# CH579M-R1.net
KiCad netlist of a schematic drawn in Altium Designer
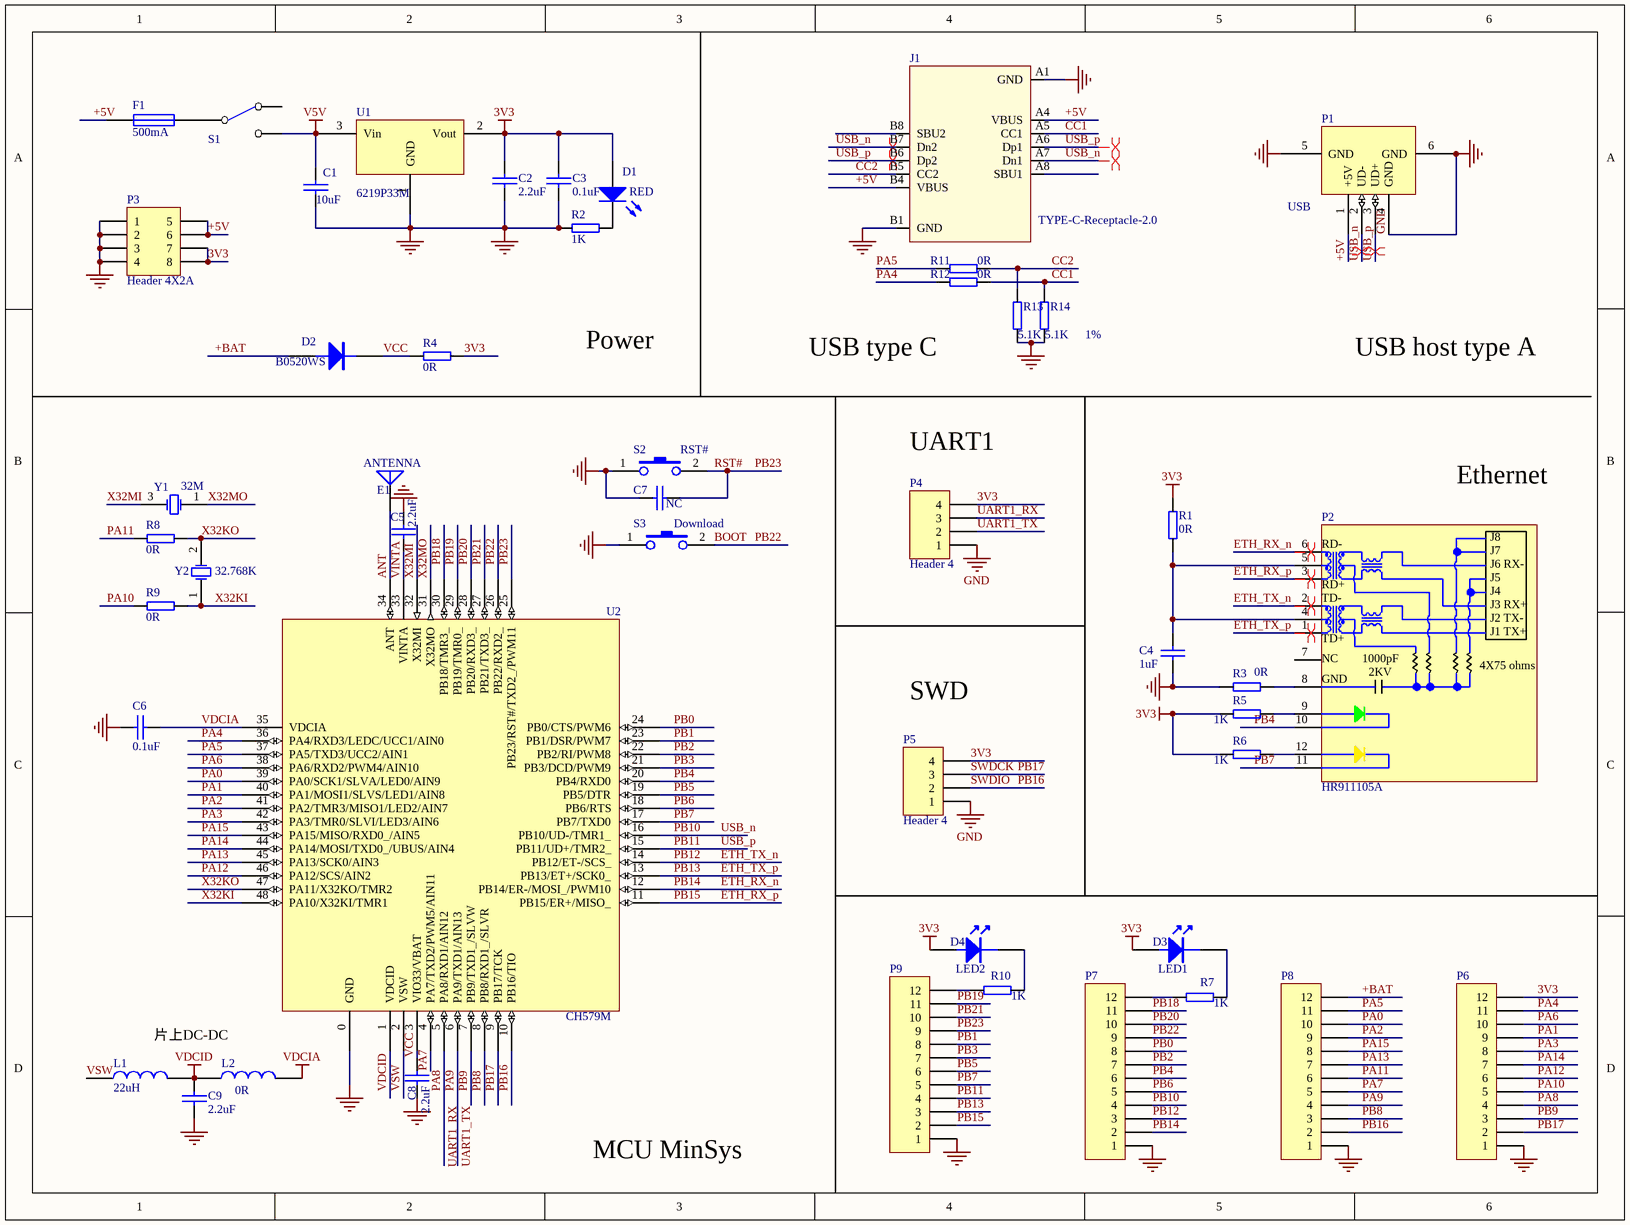
[diagram p0: CH579M-R1.SchDoc]

(export (version "E")
  (design (tool "Eeschema 10.0.6"))
  (components
    (comp (ref "C1")
      (value "10uF")
      (footprint "3216")
      (description "Capacitor")
      (libsource (lib "") (part "CAP_1"))
    )
    (comp (ref "C2")
      (value "2.2uF")
      (footprint "0603")
      (description "Capacitor")
      (libsource (lib "") (part "CAP_1"))
    )
    (comp (ref "C3")
      (value "0.1uF")
      (footprint "0603")
      (description "Capacitor")
      (libsource (lib "") (part "CAP_1"))
    )
    (comp (ref "C4")
      (value "1uF")
      (footprint "0603")
      (description "Capacitor")
      (libsource (lib "") (part "CAP_1"))
    )
    (comp (ref "C5")
      (value "2.2uF")
      (footprint "0603")
      (description "Capacitor")
      (libsource (lib "*") (part "CAP"))
    )
    (comp (ref "C6")
      (value "0.1uF")
      (footprint "0603")
      (description "Capacitor")
      (libsource (lib "*") (part "CAP"))
    )
    (comp (ref "C7")
      (value "NC")
      (footprint "0603")
      (description "Capacitor")
      (libsource (lib "*") (part "CAP"))
    )
    (comp (ref "C8")
      (value "2.2uF")
      (footprint "0603")
      (description "Capacitor")
      (libsource (lib "*") (part "CAP"))
    )
    (comp (ref "C9")
      (value "2.2uF")
      (footprint "0603")
      (description "Capacitor")
      (libsource (lib "*") (part "CAP"))
    )
    (comp (ref "D1")
      (value "RED")
      (footprint "0603+")
      (description "Typical INFRARED GaAs LED")
      (fields (field (name "PUBLISHER") "Altium Limited"))
      (libsource (lib "*") (part "LED0"))
    )
    (comp (ref "D2")
      (value "B0520WS")
      (footprint "SOD323")
      (description "Diode")
      (libsource (lib "*") (part "DIODE"))
    )
    (comp (ref "D3") (value "LED1") (footprint "0603+") (libsource (lib "*") (part "LED")))
    (comp (ref "D4") (value "LED2") (footprint "0603+") (libsource (lib "*") (part "LED")))
    (comp (ref "E1")
      (value "ANTENNA")
      (footprint "ANT-F-1-2.4G-1.6")
      (description "Generic Antenna")
      (libsource (lib "*") (part "ANTENNA"))
    )
    (comp (ref "F1")
      (value "500mA")
      (footprint "0805")
      (description "Fuse")
      (libsource (lib "wch_sch_others") (part "FUSE1"))
    )
    (comp (ref "J1")
      (value "TYPE-C-Receptacle-2.0")
      (footprint "TYPE-C-Receptacle-2.0")
      (description "Type-C USB2.0 母座")
      (libsource (lib "Miscellaneous SCH Lib") (part "TYPE-C-Receptacle-2.0"))
    )
    (comp (ref "L1") (value "22uH") (footprint "SMD-2.5*2*1.05") (libsource (lib "*") (part "INDUCTOR")))
    (comp (ref "L2") (value "0R") (footprint "0603") (libsource (lib "*") (part "INDUCTOR")))
    (comp (ref "P1")
      (value "USB")
      (footprint "USBA-L")
      (description "USB Port")
      (libsource (lib "*") (part "USB"))
    )
    (comp (ref "P2") (value "HR911105A") (footprint "HR911105A") (libsource (lib "*") (part "HR911105A")))
    (comp (ref "P3")
      (value "Header 4X2A")
      (footprint "IDC8")
      (description "Header, 4-Pin, Dual row")
      (fields (field (name "PUBLISHER") "Altium Limited"))
      (libsource (lib "Miscellaneous Connectors") (part "Header 4X2A"))
    )
    (comp (ref "P4")
      (value "Header 4")
      (footprint "HDR1X4")
      (description "Header, 4-Pin")
      (fields (field (name "PUBLISHER") "Altium Limited"))
      (libsource (lib "Miscellaneous Connectors") (part "Header 4"))
    )
    (comp (ref "P5")
      (value "Header 4")
      (footprint "HDR1X4")
      (description "Header, 4-Pin")
      (fields (field (name "PUBLISHER") "Altium Limited"))
      (libsource (lib "Miscellaneous Connectors") (part "Header 4"))
    )
    (comp (ref "P6")
      (value "Header 12")
      (footprint "SIP12 - 40mil")
      (description "Header, 12-Pin")
      (fields (field (name "PUBLISHER") "Altium Limited"))
      (libsource (lib "Miscellaneous Connectors") (part "Header 12"))
    )
    (comp (ref "P7")
      (value "Header 12")
      (footprint "SIP12 - 40mil")
      (description "Header, 12-Pin")
      (fields (field (name "PUBLISHER") "Altium Limited"))
      (libsource (lib "Miscellaneous Connectors") (part "Header 12"))
    )
    (comp (ref "P8")
      (value "Header 12")
      (footprint "SIP12 - 40mil")
      (description "Header, 12-Pin")
      (fields (field (name "PUBLISHER") "Altium Limited"))
      (libsource (lib "Miscellaneous Connectors") (part "Header 12"))
    )
    (comp (ref "P9")
      (value "Header 12")
      (footprint "SIP12 - 40mil")
      (description "Header, 12-Pin")
      (fields (field (name "PUBLISHER") "Altium Limited"))
      (libsource (lib "Miscellaneous Connectors") (part "Header 12"))
    )
    (comp (ref "R1") (value "0R") (footprint "0603") (libsource (lib "wch_sch_others") (part "RES")))
    (comp (ref "R2") (value "1K") (footprint "0603") (libsource (lib "wch_sch_others") (part "RES")))
    (comp (ref "R3") (value "0R") (footprint "0603") (libsource (lib "wch_sch_others") (part "RES")))
    (comp (ref "R4") (value "0R") (footprint "0603") (libsource (lib "wch_sch_others") (part "RES")))
    (comp (ref "R5") (value "1K") (footprint "0603") (libsource (lib "wch_sch_others") (part "RES")))
    (comp (ref "R6") (value "1K") (footprint "0603") (libsource (lib "wch_sch_others") (part "RES")))
    (comp (ref "R7") (value "1K") (footprint "0603") (libsource (lib "wch_sch_others") (part "RES")))
    (comp (ref "R8") (value "0R") (footprint "0603") (libsource (lib "wch_sch_others") (part "RES")))
    (comp (ref "R9") (value "0R") (footprint "0603") (libsource (lib "wch_sch_others") (part "RES")))
    (comp (ref "R10") (value "1K") (footprint "0603") (libsource (lib "wch_sch_others") (part "RES")))
    (comp (ref "R11") (value "0R") (footprint "0603") (libsource (lib "wch_sch_others") (part "RES")))
    (comp (ref "R12") (value "0R") (footprint "0603") (libsource (lib "wch_sch_others") (part "RES")))
    (comp (ref "R13") (value "5.1K") (footprint "0603") (libsource (lib "wch_sch_others") (part "RES")))
    (comp (ref "R14") (value "5.1K") (footprint "0603") (libsource (lib "wch_sch_others") (part "RES")))
    (comp (ref "S1") (value "SW SPDT") (footprint "KEY_B") (libsource (lib "*") (part "SW SPDT")))
    (comp (ref "S2")
      (value "RST#")
      (footprint "SMD_6.1x3.65x2.5mm-KEY")
      (libsource (lib "wch_sch_others") (part "KEY1"))
    )
    (comp (ref "S3")
      (value "Download")
      (footprint "SMD_6.1x3.65x2.5mm-KEY")
      (libsource (lib "wch_sch_others") (part "KEY1"))
    )
    (comp (ref "U1")
      (value "6219P33M")
      (footprint "SOT-23")
      (libsource (lib "wch_sch_others") (part "6219P33M"))
    )
    (comp (ref "U2")
      (value "CH579M")
      (footprint "QFN48_5X5")
      (description "ARM M0 MCU with BLE+Zigbee+Ethernet+USB")
      (libsource (lib "*") (part "CH579M"))
    )
    (comp (ref "Y1")
      (value "32M")
      (footprint "3225")
      (description "Crystal Oscillator")
      (fields (field (name "PUBLISHER") "Altium Limited"))
      (libsource (lib "*") (part "XTAL"))
    )
    (comp (ref "Y2")
      (value "32.768K")
      (footprint "fc-135")
      (description "Crystal Oscillator")
      (fields (field (name "PUBLISHER") "Altium Limited"))
      (libsource (lib "") (part "XTAL_1"))
    )
  )
  (nets
    (net (code "1") (name "/+5V") (class "Default")
      (node (ref "F1") (pin "1") (pinfunction "1_1") (pintype "passive"))
      (node (ref "J1") (pin "A4") (pinfunction "VBUS_A4") (pintype "passive"))
      (node (ref "J1") (pin "B4") (pinfunction "VBUS_B4") (pintype "passive"))
      (node (ref "P1") (pin "1") (pinfunction "+5V_1") (pintype "power_in"))
      (node (ref "P3") (pin "5") (pinfunction "5_5") (pintype "passive"))
      (node (ref "P3") (pin "6") (pinfunction "6_6") (pintype "passive"))
    )
    (net (code "2") (name "/+BAT") (class "Default")
      (node (ref "D2") (pin "1") (pinfunction "A_1") (pintype "passive"))
      (node (ref "P8") (pin "12") (pinfunction "12_12") (pintype "passive"))
    )
    (net (code "3") (name "/ANT") (class "Default")
      (node (ref "E1") (pin "1") (pinfunction "A_1") (pintype "passive"))
      (node (ref "U2") (pin "34") (pinfunction "ANT_34") (pintype "bidirectional"))
    )
    (net (code "4") (name "/BOOT") (class "Default")
      (node (ref "P7") (pin "9") (pinfunction "9_9") (pintype "passive"))
      (node (ref "S3") (pin "2") (pinfunction "2_2") (pintype "passive"))
      (node (ref "U2") (pin "26") (pinfunction "PB22/RXD2__26") (pintype "bidirectional"))
    )
    (net (code "5") (name "/CC1") (class "Default")
      (node (ref "J1") (pin "A5") (pinfunction "CC1_A5") (pintype "passive"))
      (node (ref "R12") (pin "2") (pintype "passive"))
      (node (ref "R14") (pin "1") (pintype "passive"))
    )
    (net (code "6") (name "/CC2") (class "Default")
      (node (ref "J1") (pin "B5") (pinfunction "CC2_B5") (pintype "passive"))
      (node (ref "R11") (pin "2") (pintype "passive"))
      (node (ref "R13") (pin "1") (pintype "passive"))
    )
    (net (code "7") (name "/ETH_RX_n") (class "Default")
      (node (ref "P2") (pin "6") (pintype "passive"))
      (node (ref "P7") (pin "2") (pinfunction "2_2") (pintype "passive"))
      (node (ref "U2") (pin "12") (pinfunction "PB14/ER-/MOSI_/PWM10_12") (pintype "bidirectional"))
    )
    (net (code "8") (name "/ETH_RX_p") (class "Default")
      (node (ref "P2") (pin "3") (pintype "passive"))
      (node (ref "P9") (pin "2") (pinfunction "2_2") (pintype "passive"))
      (node (ref "U2") (pin "11") (pinfunction "PB15/ER+/MISO__11") (pintype "bidirectional"))
    )
    (net (code "9") (name "/ETH_TX_n") (class "Default")
      (node (ref "P2") (pin "2") (pintype "passive"))
      (node (ref "P7") (pin "3") (pinfunction "3_3") (pintype "passive"))
      (node (ref "U2") (pin "14") (pinfunction "PB12/ET-/SCS__14") (pintype "bidirectional"))
    )
    (net (code "10") (name "/ETH_TX_p") (class "Default")
      (node (ref "P2") (pin "1") (pintype "passive"))
      (node (ref "P9") (pin "3") (pinfunction "3_3") (pintype "passive"))
      (node (ref "U2") (pin "13") (pinfunction "PB13/ET+/SCK0__13") (pintype "bidirectional"))
    )
    (net (code "11") (name "/PA0") (class "Default")
      (node (ref "P8") (pin "10") (pinfunction "10_10") (pintype "passive"))
      (node (ref "U2") (pin "39") (pinfunction "PA0/SCK1/SLVA/LED0/AIN9_39") (pintype "bidirectional"))
    )
    (net (code "12") (name "/PA1") (class "Default")
      (node (ref "P6") (pin "9") (pinfunction "9_9") (pintype "passive"))
      (node (ref "U2") (pin "40") (pinfunction "PA1/MOSI1/SLVS/LED1/AIN8_40") (pintype "bidirectional"))
    )
    (net (code "13") (name "/PA2") (class "Default")
      (node (ref "P8") (pin "9") (pinfunction "9_9") (pintype "passive"))
      (node (ref "U2") (pin "41") (pinfunction "PA2/TMR3/MISO1/LED2/AIN7_41") (pintype "bidirectional"))
    )
    (net (code "14") (name "/PA3") (class "Default")
      (node (ref "P6") (pin "8") (pinfunction "8_8") (pintype "passive"))
      (node (ref "U2") (pin "42") (pinfunction "PA3/TMR0/SLVI/LED3/AIN6_42") (pintype "bidirectional"))
    )
    (net (code "15") (name "/PA4") (class "Default")
      (node (ref "P6") (pin "11") (pinfunction "11_11") (pintype "passive"))
      (node (ref "R12") (pin "1") (pintype "passive"))
      (node (ref "U2") (pin "36") (pinfunction "PA4/RXD3/LEDC/UCC1/AIN0_36") (pintype "bidirectional"))
    )
    (net (code "16") (name "/PA5") (class "Default")
      (node (ref "P8") (pin "11") (pinfunction "11_11") (pintype "passive"))
      (node (ref "R11") (pin "1") (pintype "passive"))
      (node (ref "U2") (pin "37") (pinfunction "PA5/TXD3/UCC2/AIN1_37") (pintype "bidirectional"))
    )
    (net (code "17") (name "/PA6") (class "Default")
      (node (ref "P6") (pin "10") (pinfunction "10_10") (pintype "passive"))
      (node (ref "U2") (pin "38") (pinfunction "PA6/RXD2/PWM4/AIN10_38") (pintype "bidirectional"))
    )
    (net (code "18") (name "/PA7") (class "Default")
      (node (ref "P8") (pin "5") (pinfunction "5_5") (pintype "passive"))
      (node (ref "U2") (pin "4") (pinfunction "PA7/TXD2/PWM5/AIN11_4") (pintype "bidirectional"))
    )
    (net (code "19") (name "/PA8") (class "Default")
      (node (ref "P4") (pin "3") (pinfunction "3_3") (pintype "passive"))
      (node (ref "P6") (pin "4") (pinfunction "4_4") (pintype "passive"))
      (node (ref "U2") (pin "5") (pinfunction "PA8/RXD1/AIN12_5") (pintype "bidirectional"))
    )
    (net (code "20") (name "/PA9") (class "Default")
      (node (ref "P4") (pin "2") (pinfunction "2_2") (pintype "passive"))
      (node (ref "P8") (pin "4") (pinfunction "4_4") (pintype "passive"))
      (node (ref "U2") (pin "6") (pinfunction "PA9/TXD1/AIN13_6") (pintype "bidirectional"))
    )
    (net (code "21") (name "/PA10") (class "Default")
      (node (ref "P6") (pin "5") (pinfunction "5_5") (pintype "passive"))
      (node (ref "R9") (pin "1") (pintype "passive"))
    )
    (net (code "22") (name "/PA11") (class "Default")
      (node (ref "P8") (pin "6") (pinfunction "6_6") (pintype "passive"))
      (node (ref "R8") (pin "1") (pintype "passive"))
    )
    (net (code "23") (name "/PA12") (class "Default")
      (node (ref "P6") (pin "6") (pinfunction "6_6") (pintype "passive"))
      (node (ref "U2") (pin "46") (pinfunction "PA12/SCS/AIN2_46") (pintype "bidirectional"))
    )
    (net (code "24") (name "/PA13") (class "Default")
      (node (ref "P8") (pin "7") (pinfunction "7_7") (pintype "passive"))
      (node (ref "U2") (pin "45") (pinfunction "PA13/SCK0/AIN3_45") (pintype "bidirectional"))
    )
    (net (code "25") (name "/PA14") (class "Default")
      (node (ref "P6") (pin "7") (pinfunction "7_7") (pintype "passive"))
      (node (ref "U2") (pin "44") (pinfunction "PA14/MOSI/TXD0_/UBUS/AIN4_44") (pintype "bidirectional"))
    )
    (net (code "26") (name "/PA15") (class "Default")
      (node (ref "P8") (pin "8") (pinfunction "8_8") (pintype "passive"))
      (node (ref "U2") (pin "43") (pinfunction "PA15/MISO/RXD0_/AIN5_43") (pintype "bidirectional"))
    )
    (net (code "27") (name "/PB0") (class "Default")
      (node (ref "P7") (pin "8") (pinfunction "8_8") (pintype "passive"))
      (node (ref "U2") (pin "24") (pinfunction "PB0/CTS/PWM6_24") (pintype "bidirectional"))
    )
    (net (code "28") (name "/PB1") (class "Default")
      (node (ref "P9") (pin "8") (pinfunction "8_8") (pintype "passive"))
      (node (ref "U2") (pin "23") (pinfunction "PB1/DSR/PWM7_23") (pintype "bidirectional"))
    )
    (net (code "29") (name "/PB2") (class "Default")
      (node (ref "P7") (pin "7") (pinfunction "7_7") (pintype "passive"))
      (node (ref "U2") (pin "22") (pinfunction "PB2/RI/PWM8_22") (pintype "bidirectional"))
    )
    (net (code "30") (name "/PB3") (class "Default")
      (node (ref "P9") (pin "7") (pinfunction "7_7") (pintype "passive"))
      (node (ref "U2") (pin "21") (pinfunction "PB3/DCD/PWM9_21") (pintype "bidirectional"))
    )
    (net (code "31") (name "/PB4") (class "Default")
      (node (ref "P2") (pin "10") (pintype "passive"))
      (node (ref "P7") (pin "6") (pinfunction "6_6") (pintype "passive"))
      (node (ref "U2") (pin "20") (pinfunction "PB4/RXD0_20") (pintype "bidirectional"))
    )
    (net (code "32") (name "/PB5") (class "Default")
      (node (ref "P9") (pin "6") (pinfunction "6_6") (pintype "passive"))
      (node (ref "U2") (pin "19") (pinfunction "PB5/DTR_19") (pintype "bidirectional"))
    )
    (net (code "33") (name "/PB6") (class "Default")
      (node (ref "P7") (pin "5") (pinfunction "5_5") (pintype "passive"))
      (node (ref "U2") (pin "18") (pinfunction "PB6/RTS_18") (pintype "bidirectional"))
    )
    (net (code "34") (name "/PB7") (class "Default")
      (node (ref "P2") (pin "11") (pintype "passive"))
      (node (ref "P9") (pin "5") (pinfunction "5_5") (pintype "passive"))
      (node (ref "U2") (pin "17") (pinfunction "PB7/TXD0_17") (pintype "bidirectional"))
    )
    (net (code "35") (name "/PB8") (class "Default")
      (node (ref "P8") (pin "3") (pinfunction "3_3") (pintype "passive"))
      (node (ref "U2") (pin "8") (pinfunction "PB8/RXD1_/SLVR_8") (pintype "bidirectional"))
    )
    (net (code "36") (name "/PB9") (class "Default")
      (node (ref "P6") (pin "3") (pinfunction "3_3") (pintype "passive"))
      (node (ref "U2") (pin "7") (pinfunction "PB9/TXD1_/SLVW_7") (pintype "bidirectional"))
    )
    (net (code "37") (name "/PB10") (class "Default")
      (node (ref "J1") (pin "A7") (pinfunction "Dn1_A7") (pintype "passive"))
      (node (ref "J1") (pin "B7") (pinfunction "Dn2_B7") (pintype "passive"))
      (node (ref "P1") (pin "2") (pinfunction "UD-_2") (pintype "bidirectional"))
      (node (ref "P7") (pin "4") (pinfunction "4_4") (pintype "passive"))
      (node (ref "U2") (pin "16") (pinfunction "PB10/UD-/TMR1__16") (pintype "bidirectional"))
    )
    (net (code "38") (name "/PB11") (class "Default")
      (node (ref "J1") (pin "A6") (pinfunction "Dp1_A6") (pintype "passive"))
      (node (ref "J1") (pin "B6") (pinfunction "Dp2_B6") (pintype "passive"))
      (node (ref "P1") (pin "3") (pinfunction "UD+_3") (pintype "bidirectional"))
      (node (ref "P9") (pin "4") (pinfunction "4_4") (pintype "passive"))
      (node (ref "U2") (pin "15") (pinfunction "PB11/UD+/TMR2__15") (pintype "bidirectional"))
    )
    (net (code "39") (name "/PB16") (class "Default")
      (node (ref "P5") (pin "2") (pinfunction "2_2") (pintype "passive"))
      (node (ref "P8") (pin "2") (pinfunction "2_2") (pintype "passive"))
      (node (ref "U2") (pin "10") (pinfunction "PB16/TIO_10") (pintype "bidirectional"))
    )
    (net (code "40") (name "/PB17") (class "Default")
      (node (ref "P5") (pin "3") (pinfunction "3_3") (pintype "passive"))
      (node (ref "P6") (pin "2") (pinfunction "2_2") (pintype "passive"))
      (node (ref "U2") (pin "9") (pinfunction "PB17/TCK_9") (pintype "bidirectional"))
    )
    (net (code "41") (name "/PB18") (class "Default")
      (node (ref "P7") (pin "11") (pinfunction "11_11") (pintype "passive"))
      (node (ref "U2") (pin "30") (pinfunction "PB18/TMR3__30") (pintype "bidirectional"))
    )
    (net (code "42") (name "/PB19") (class "Default")
      (node (ref "P9") (pin "11") (pinfunction "11_11") (pintype "passive"))
      (node (ref "U2") (pin "29") (pinfunction "PB19/TMR0__29") (pintype "bidirectional"))
    )
    (net (code "43") (name "/PB20") (class "Default")
      (node (ref "P7") (pin "10") (pinfunction "10_10") (pintype "passive"))
      (node (ref "U2") (pin "28") (pinfunction "PB20/RXD3__28") (pintype "bidirectional"))
    )
    (net (code "44") (name "/PB21") (class "Default")
      (node (ref "P9") (pin "10") (pinfunction "10_10") (pintype "passive"))
      (node (ref "U2") (pin "27") (pinfunction "PB21/TXD3__27") (pintype "bidirectional"))
    )
    (net (code "45") (name "/PB23") (class "Default")
      (node (ref "C7") (pin "2") (pinfunction "2_2") (pintype "passive"))
      (node (ref "P9") (pin "9") (pinfunction "9_9") (pintype "passive"))
      (node (ref "S2") (pin "2") (pinfunction "2_2") (pintype "passive"))
      (node (ref "U2") (pin "25") (pinfunction "PB23/RST#/TXD2_/PWM11_25") (pintype "bidirectional"))
    )
    (net (code "46") (name "/VCC") (class "Default")
      (node (ref "C8") (pin "2") (pinfunction "2_2") (pintype "passive"))
      (node (ref "D2") (pin "2") (pinfunction "K_2") (pintype "passive"))
      (node (ref "R4") (pin "2") (pintype "passive"))
      (node (ref "U2") (pin "3") (pinfunction "VIO33/VBAT_3") (pintype "power_in"))
    )
    (net (code "47") (name "/VINTA") (class "Default")
      (node (ref "C5") (pin "1") (pinfunction "1_1") (pintype "passive"))
      (node (ref "U2") (pin "33") (pinfunction "VINTA_33") (pintype "power_in"))
    )
    (net (code "48") (name "/VSW") (class "Default")
      (node (ref "L1") (pin "1") (pinfunction "1_1") (pintype "passive"))
      (node (ref "U2") (pin "2") (pinfunction "VSW_2") (pintype "power_in"))
    )
    (net (code "49") (name "/X32KI") (class "Default")
      (node (ref "R9") (pin "2") (pintype "passive"))
      (node (ref "U2") (pin "48") (pinfunction "PA10/X32KI/TMR1_48") (pintype "bidirectional"))
      (node (ref "Y2") (pin "1") (pinfunction "OSC1_1") (pintype "passive"))
    )
    (net (code "50") (name "/X32KO") (class "Default")
      (node (ref "R8") (pin "2") (pintype "passive"))
      (node (ref "U2") (pin "47") (pinfunction "PA11/X32KO/TMR2_47") (pintype "bidirectional"))
      (node (ref "Y2") (pin "2") (pinfunction "OSC2_2") (pintype "passive"))
    )
    (net (code "51") (name "/X32MI") (class "Default")
      (node (ref "U2") (pin "32") (pinfunction "X32MI_32") (pintype "input"))
      (node (ref "Y1") (pin "3") (pinfunction "OSC2_3") (pintype "passive"))
    )
    (net (code "52") (name "/X32MO") (class "Default")
      (node (ref "U2") (pin "31") (pinfunction "X32MO_31") (pintype "output"))
      (node (ref "Y1") (pin "1") (pinfunction "OSC1_1") (pintype "passive"))
    )
    (net (code "53") (name "3V3") (class "Default")
      (node (ref "C2") (pin "1") (pinfunction "1_1") (pintype "passive"))
      (node (ref "C3") (pin "1") (pinfunction "1_1") (pintype "passive"))
      (node (ref "D1") (pin "1") (pinfunction "A_1") (pintype "passive"))
      (node (ref "D3") (pin "1") (pinfunction "1_1") (pintype "passive"))
      (node (ref "D4") (pin "1") (pinfunction "1_1") (pintype "passive"))
      (node (ref "P3") (pin "7") (pinfunction "7_7") (pintype "passive"))
      (node (ref "P3") (pin "8") (pinfunction "8_8") (pintype "passive"))
      (node (ref "P4") (pin "4") (pinfunction "4_4") (pintype "passive"))
      (node (ref "P5") (pin "4") (pinfunction "4_4") (pintype "passive"))
      (node (ref "P6") (pin "12") (pinfunction "12_12") (pintype "passive"))
      (node (ref "R1") (pin "2") (pintype "passive"))
      (node (ref "R4") (pin "1") (pintype "passive"))
      (node (ref "R5") (pin "1") (pintype "passive"))
      (node (ref "R6") (pin "1") (pintype "passive"))
      (node (ref "U1") (pin "2") (pinfunction "Vout_2") (pintype "passive"))
    )
    (net (code "54") (name "GND") (class "Default")
      (node (ref "C1") (pin "2") (pinfunction "2_2") (pintype "passive"))
      (node (ref "C2") (pin "2") (pinfunction "2_2") (pintype "passive"))
      (node (ref "C3") (pin "2") (pinfunction "2_2") (pintype "passive"))
      (node (ref "C4") (pin "1") (pinfunction "1_1") (pintype "passive"))
      (node (ref "C5") (pin "2") (pinfunction "2_2") (pintype "passive"))
      (node (ref "C6") (pin "2") (pinfunction "2_2") (pintype "passive"))
      (node (ref "C7") (pin "1") (pinfunction "1_1") (pintype "passive"))
      (node (ref "C8") (pin "1") (pinfunction "1_1") (pintype "passive"))
      (node (ref "C9") (pin "1") (pinfunction "1_1") (pintype "passive"))
      (node (ref "J1") (pin "A1") (pinfunction "GND_A1") (pintype "passive"))
      (node (ref "J1") (pin "B1") (pinfunction "GND_B1") (pintype "passive"))
      (node (ref "P1") (pin "4") (pinfunction "GND_4") (pintype "power_in"))
      (node (ref "P1") (pin "5") (pinfunction "GND_5") (pintype "power_in"))
      (node (ref "P1") (pin "6") (pinfunction "GND_6") (pintype "power_in"))
      (node (ref "P3") (pin "1") (pinfunction "1_1") (pintype "passive"))
      (node (ref "P3") (pin "2") (pinfunction "2_2") (pintype "passive"))
      (node (ref "P3") (pin "3") (pinfunction "3_3") (pintype "passive"))
      (node (ref "P3") (pin "4") (pinfunction "4_4") (pintype "passive"))
      (node (ref "P4") (pin "1") (pinfunction "1_1") (pintype "passive"))
      (node (ref "P5") (pin "1") (pinfunction "1_1") (pintype "passive"))
      (node (ref "P6") (pin "1") (pinfunction "1_1") (pintype "passive"))
      (node (ref "P7") (pin "1") (pinfunction "1_1") (pintype "passive"))
      (node (ref "P8") (pin "1") (pinfunction "1_1") (pintype "passive"))
      (node (ref "P9") (pin "1") (pinfunction "1_1") (pintype "passive"))
      (node (ref "R13") (pin "2") (pintype "passive"))
      (node (ref "R14") (pin "2") (pintype "passive"))
      (node (ref "R2") (pin "2") (pintype "passive"))
      (node (ref "R3") (pin "1") (pintype "passive"))
      (node (ref "S2") (pin "1") (pinfunction "1_1") (pintype "passive"))
      (node (ref "S3") (pin "1") (pinfunction "1_1") (pintype "passive"))
      (node (ref "U1") (pin "1") (pinfunction "GND_1") (pintype "passive"))
      (node (ref "U2") (pin "0") (pinfunction "GND_0") (pintype "power_in"))
    )
    (net (code "55") (name "Net-(C4-Pad2)") (class "Default")
      (node (ref "C4") (pin "2") (pinfunction "2_2") (pintype "passive"))
      (node (ref "P2") (pin "4") (pintype "passive"))
      (node (ref "P2") (pin "5") (pintype "passive"))
      (node (ref "R1") (pin "1") (pintype "passive"))
    )
    (net (code "56") (name "Net-(D1-K)") (class "Default")
      (node (ref "D1") (pin "2") (pinfunction "K_2") (pintype "passive"))
      (node (ref "R2") (pin "1") (pintype "passive"))
    )
    (net (code "57") (name "Net-(D3-Pad2)") (class "Default")
      (node (ref "D3") (pin "2") (pinfunction "2_2") (pintype "passive"))
      (node (ref "R7") (pin "2") (pintype "passive"))
    )
    (net (code "58") (name "Net-(D4-Pad2)") (class "Default")
      (node (ref "D4") (pin "2") (pinfunction "2_2") (pintype "passive"))
      (node (ref "R10") (pin "2") (pintype "passive"))
    )
    (net (code "59") (name "Net-(P2-Pad8)") (class "Default")
      (node (ref "P2") (pin "8") (pintype "passive"))
      (node (ref "R3") (pin "2") (pintype "passive"))
    )
    (net (code "60") (name "Net-(P2-Pad9)") (class "Default")
      (node (ref "P2") (pin "9") (pintype "passive"))
      (node (ref "R5") (pin "2") (pintype "passive"))
    )
    (net (code "61") (name "Net-(P2-Pad12)") (class "Default")
      (node (ref "P2") (pin "12") (pintype "passive"))
      (node (ref "R6") (pin "2") (pintype "passive"))
    )
    (net (code "62") (name "Net-(P7-Pad12)") (class "Default")
      (node (ref "P7") (pin "12") (pinfunction "12_12") (pintype "passive"))
      (node (ref "R7") (pin "1") (pintype "passive"))
    )
    (net (code "63") (name "Net-(P9-Pad12)") (class "Default")
      (node (ref "P9") (pin "12") (pinfunction "12_12") (pintype "passive"))
      (node (ref "R10") (pin "1") (pintype "passive"))
    )
    (net (code "64") (name "Net-(S1-COMMON)") (class "Default")
      (node (ref "F1") (pin "2") (pinfunction "2_2") (pintype "passive"))
      (node (ref "S1") (pin "1") (pinfunction "COMMON_1") (pintype "passive"))
    )
    (net (code "65") (name "V5V") (class "Default")
      (node (ref "C1") (pin "1") (pinfunction "1_1") (pintype "passive"))
      (node (ref "S1") (pin "2") (pinfunction "NC_2") (pintype "passive"))
      (node (ref "U1") (pin "3") (pinfunction "Vin_3") (pintype "passive"))
    )
    (net (code "66") (name "VDCIA") (class "Default")
      (node (ref "C6") (pin "1") (pinfunction "1_1") (pintype "passive"))
      (node (ref "L2") (pin "2") (pinfunction "2_2") (pintype "passive"))
      (node (ref "U2") (pin "35") (pinfunction "VDCIA_35") (pintype "power_in"))
    )
    (net (code "67") (name "VDCID") (class "Default")
      (node (ref "C9") (pin "2") (pinfunction "2_2") (pintype "passive"))
      (node (ref "L1") (pin "2") (pinfunction "2_2") (pintype "passive"))
      (node (ref "L2") (pin "1") (pinfunction "1_1") (pintype "passive"))
      (node (ref "U2") (pin "1") (pinfunction "VDCID_1") (pintype "power_in"))
    )
    (net (code "68") (name "unconnected-(J1-SBU1-PadA8)") (class "Default")
      (node (ref "J1") (pin "A8") (pinfunction "SBU1_A8") (pintype "passive"))
    )
    (net (code "69") (name "unconnected-(J1-SBU2-PadB8)") (class "Default")
      (node (ref "J1") (pin "B8") (pinfunction "SBU2_B8") (pintype "passive"))
    )
    (net (code "70") (name "unconnected-(P2-Pad7)") (class "Default")
      (node (ref "P2") (pin "7") (pintype "passive"))
    )
    (net (code "71") (name "unconnected-(S1-NO-Pad3)") (class "Default")
      (node (ref "S1") (pin "3") (pinfunction "NO_3") (pintype "passive"))
    )
  )
)
